# Arduino_Electronic_Load_Ver07.net
KiCad netlist of a schematic drawn in EAGLE
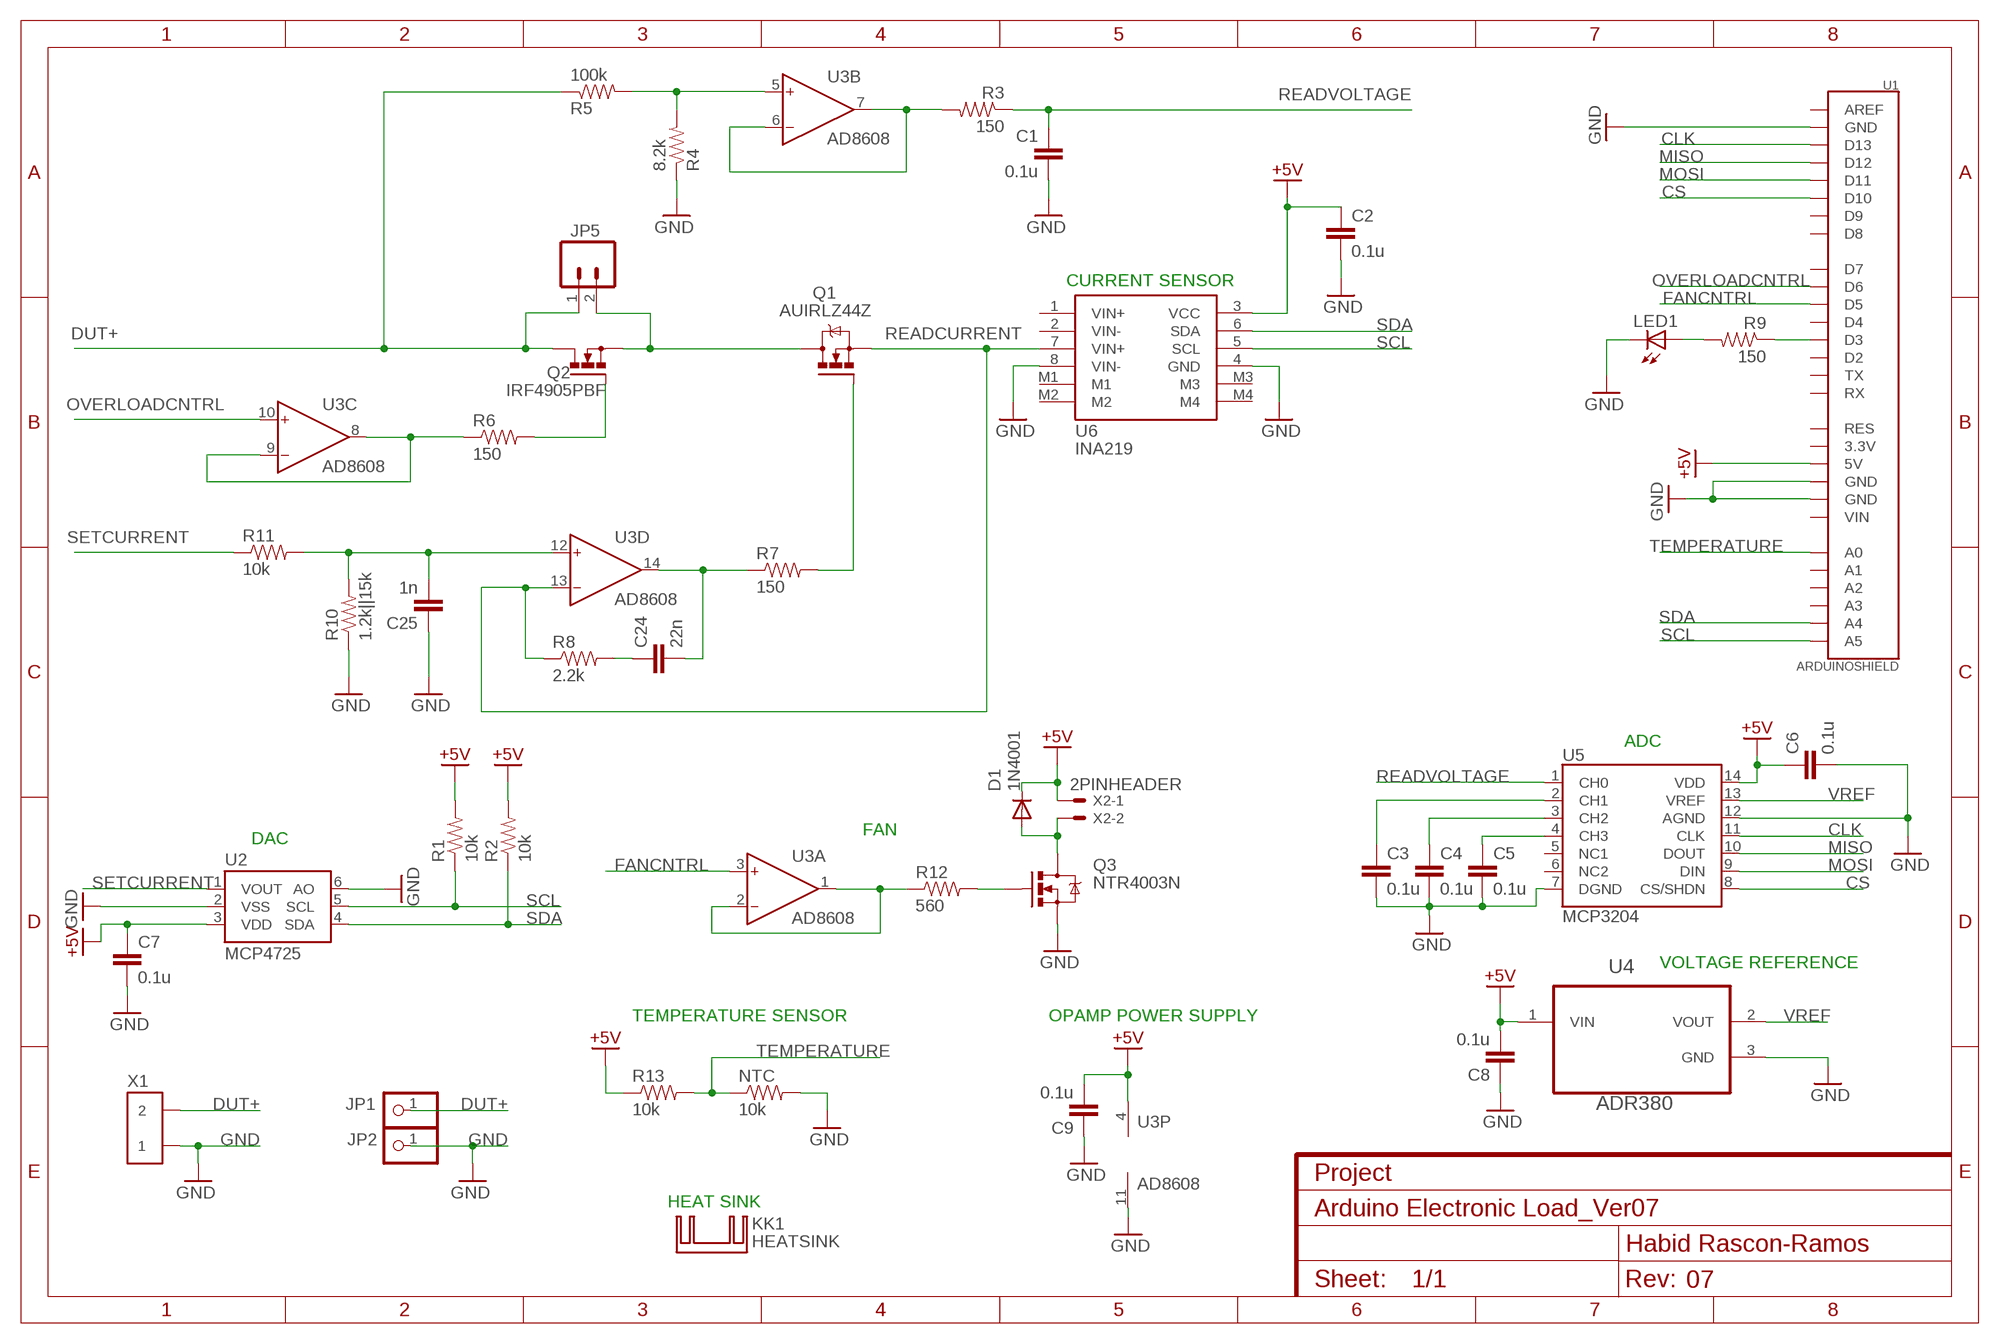
[diagram p0: schematic, sheet 1]

(export (version "E")
  (design (tool "Eeschema 10.0.6"))
  (components
    (comp (ref "C1")
      (value "0.1u")
      (footprint "eagle-import:0603-CAP")
      (description "CAP CER 0.1UF 16V X7R 0603")
      (fields
        (field (name "MANUFACTURER") "Murata Electronics North America")
        (field (name "MFG_PART_NUMBER") "GRM188R71C104KA01D")
      )
      (libsource (lib "eagle-import") (part "CAP0603-CAP"))
    )
    (comp (ref "C2")
      (value "0.1u")
      (footprint "eagle-import:0603-CAP")
      (description "CAP CER 0.1UF 16V X7R 0603")
      (fields
        (field (name "MANUFACTURER") "Murata Electronics North America")
        (field (name "MFG_PART_NUMBER") "GRM188R71C104KA01D")
      )
      (libsource (lib "eagle-import") (part "CAP0603-CAP"))
    )
    (comp (ref "C3")
      (value "0.1u")
      (footprint "eagle-import:0603-CAP")
      (description "CAP CER 0.1UF 16V X7R 0603")
      (fields
        (field (name "MANUFACTURER") "Murata Electronics North America")
        (field (name "MFG_PART_NUMBER") "GRM188R71C104KA01D")
      )
      (libsource (lib "eagle-import") (part "CAP0603-CAP"))
    )
    (comp (ref "C4")
      (value "0.1u")
      (footprint "eagle-import:0603-CAP")
      (description "CAP CER 0.1UF 16V X7R 0603")
      (fields
        (field (name "MANUFACTURER") "Murata Electronics North America")
        (field (name "MFG_PART_NUMBER") "GRM188R71C104KA01D")
      )
      (libsource (lib "eagle-import") (part "CAP0603-CAP"))
    )
    (comp (ref "C5")
      (value "0.1u")
      (footprint "eagle-import:0603-CAP")
      (description "CAP CER 0.1UF 16V X7R 0603")
      (fields
        (field (name "MANUFACTURER") "Murata Electronics North America")
        (field (name "MFG_PART_NUMBER") "GRM188R71C104KA01D")
      )
      (libsource (lib "eagle-import") (part "CAP0603-CAP"))
    )
    (comp (ref "C6")
      (value "0.1u")
      (footprint "eagle-import:0603-CAP")
      (description "CAP CER 0.1UF 16V X7R 0603")
      (fields
        (field (name "MANUFACTURER") "Murata Electronics North America")
        (field (name "MFG_PART_NUMBER") "GRM188R71C104KA01D")
      )
      (libsource (lib "eagle-import") (part "CAP0603-CAP"))
    )
    (comp (ref "C7")
      (value "0.1u")
      (footprint "eagle-import:0603-CAP")
      (description "CAP CER 0.1UF 16V X7R 0603")
      (fields
        (field (name "MANUFACTURER") "Murata Electronics North America")
        (field (name "MFG_PART_NUMBER") "GRM188R71C104KA01D")
      )
      (libsource (lib "eagle-import") (part "CAP0603-CAP"))
    )
    (comp (ref "C8")
      (value "0.1u")
      (footprint "eagle-import:0603-CAP")
      (description "CAP CER 0.1UF 16V X7R 0603")
      (fields
        (field (name "MANUFACTURER") "Murata Electronics North America")
        (field (name "MFG_PART_NUMBER") "GRM188R71C104KA01D")
      )
      (libsource (lib "eagle-import") (part "CAP0603-CAP"))
    )
    (comp (ref "C9")
      (value "0.1u")
      (footprint "eagle-import:0603-CAP")
      (description "CAP CER 0.1UF 16V X7R 0603")
      (fields
        (field (name "MANUFACTURER") "Murata Electronics North America")
        (field (name "MFG_PART_NUMBER") "GRM188R71C104KA01D")
      )
      (libsource (lib "eagle-import") (part "CAP0603-CAP"))
    )
    (comp (ref "C24")
      (value "22n")
      (footprint "eagle-import:0603-CAP")
      (description "CAP CER 0.022UF 16V X7R 0603")
      (fields
        (field (name "MANUFACTURER") "Murata Electronics North America")
        (field (name "MFG_PART_NUMBER") "GRM188R71C223KA01D")
      )
      (libsource (lib "eagle-import") (part "CAP0603-CAP"))
    )
    (comp (ref "C25")
      (value "1n")
      (footprint "eagle-import:0603-CAP")
      (description "CAP CER 1000PF 50V X7R 0603")
      (fields
        (field (name "MANUFACTURER") "Murata Electronics North America")
        (field (name "MFG_PART_NUMBER") "GRM188R71H102KA01D")
      )
      (libsource (lib "eagle-import") (part "CAP0603-CAP"))
    )
    (comp (ref "D1")
      (value "1N4001")
      (footprint "eagle-import:DIODE-1N4001")
      (description "DIODE GEN PURP 50V 1A DO41")
      (fields
        (field (name "MANUFACTURER") "Fairchild Semiconductor")
        (field (name "VENDOR_PART_NUM") "1N4001FSCT-ND")
      )
      (libsource (lib "eagle-import") (part "DIODEPTH"))
    )
    (comp (ref "JP1")
      (value "N/A")
      (footprint "eagle-import:PINHEAD_1X01")
      (libsource (lib "eagle-import") (part "PINHEAD_PINHD-1X1"))
    )
    (comp (ref "JP2")
      (value "N/A")
      (footprint "eagle-import:PINHEAD_1X01")
      (libsource (lib "eagle-import") (part "PINHEAD_PINHD-1X1"))
    )
    (comp (ref "JP5")
      (value "2PINHEADER")
      (footprint "eagle-import:1X02_LONGPADS")
      (description "CONN HEADER VERT SGL 2POS GOLD")
      (fields (field (name "MANUFACTURER") "3M") (field (name "MFG_PART_NUMBER") "961102-6404-AR"))
      (libsource (lib "eagle-import") (part "M02"))
    )
    (comp (ref "KK1")
      (value "HEATSINK")
      (footprint "eagle-import:HEATSINK_SK129-HOLE")
      (description "HEAT SINK, EXTRUDED, PCB MOUNT")
      (fields
        (field (name "MANUFACTURER") "FISCHER ELEKTRONIK")
        (field (name "MFG_PART_NUMBER") "SK 129 25,4 STS")
      )
      (libsource (lib "eagle-import") (part "HEATSINK_SK129"))
    )
    (comp (ref "LED1")
      (value "REDLED")
      (footprint "eagle-import:LED5MM")
      (description "LED RED DIFF 5MM ROUND T/H")
      (fields (field (name "MANUFACTURER") "Lite-On Inc.") (field (name "MFG_PART_NUMBER") "LTL2R3KRD-EM"))
      (libsource (lib "eagle-import") (part "LED5MM"))
    )
    (comp (ref "NTC")
      (value "10k")
      (footprint "eagle-import:0402-RES")
      (description "THERMISTOR 10K OHM NTC 0402 SMD")
      (fields
        (field (name "MANUFACTURER") "Murata Electronics North America")
        (field (name "MFG_PART_NUMBER") "NCP15XH103F03RC")
      )
      (libsource (lib "eagle-import") (part "RESISTOR0402-RES"))
    )
    (comp (ref "Q1")
      (value "AUIRLZ44Z")
      (footprint "eagle-import:TO220BV_1")
      (description "MOSFET Transistor, N Channel, 51 A, 55 V, TO-220AB")
      (fields
        (field (name "MANUFACTURER") "INTERNATIONAL RECTIFIER")
        (field (name "VENDOR_PART_NUM") "54T9019")
      )
      (libsource (lib "eagle-import") (part "IRLZ44Z"))
    )
    (comp (ref "Q2")
      (value "IRF4905PBF")
      (footprint "eagle-import:TO220BV")
      (description "MOSFET P-CH 55V 74A TO-220AB")
      (fields
        (field (name "MANUFACTURER") "Infineon Technologies Americas Corp.")
        (field (name "VENDOR_PART_NUM") "IRF4905PBF-ND")
      )
      (libsource (lib "eagle-import") (part "PMOSFET_NTO220BV"))
    )
    (comp (ref "Q3")
      (value "NTR4003N")
      (footprint "eagle-import:SOT23-3")
      (description "MOSFET N-CH 30V 500MA SOT-23")
      (fields (field (name "MANUFACTURER") "ON Semiconductor") (field (name "MFG_PART_NUMBER") "NTR4003NT1G"))
      (libsource (lib "eagle-import") (part "MOSFET-NCHANNELAO3404A"))
    )
    (comp (ref "R1")
      (value "10k")
      (footprint "eagle-import:0603-RES")
      (description "RES SMD 10K OHM 1% 1/10W 0603")
      (fields (field (name "MANUFACTURER") "Yageo") (field (name "MFG_PART_NUMBER") "RC0603FR-0710KL"))
      (libsource (lib "eagle-import") (part "RESISTOR0603-RES"))
    )
    (comp (ref "R2")
      (value "10k")
      (footprint "eagle-import:0603-RES")
      (description "RES SMD 10K OHM 1% 1/10W 0603")
      (fields (field (name "MANUFACTURER") "Yageo") (field (name "MFG_PART_NUMBER") "RC0603FR-0710KL"))
      (libsource (lib "eagle-import") (part "RESISTOR0603-RES"))
    )
    (comp (ref "R3")
      (value "150")
      (footprint "eagle-import:0603-RES")
      (description "RES SMD 150 OHM 1% 1/10W 0603")
      (fields (field (name "MANUFACTURER") "Yageo") (field (name "MFG_PART_NUMBER") "RC0603FR-07150RL"))
      (libsource (lib "eagle-import") (part "RESISTOR0603-RES"))
    )
    (comp (ref "R4")
      (value "8.2k")
      (footprint "eagle-import:0603-RES")
      (description "RES SMD 8.2K OHM 1% 1/10W 0603")
      (fields (field (name "MANUFACTURER") "Yageo") (field (name "MFG_PART_NUMBER") "RC0603FR-078K2L"))
      (libsource (lib "eagle-import") (part "RESISTOR0603-RES"))
    )
    (comp (ref "R5")
      (value "100k")
      (footprint "eagle-import:0603-RES")
      (description "RES SMD 100K OHM 1% 1/10W 0603")
      (fields (field (name "MANUFACTURER") "Yageo") (field (name "MFG_PART_NUMBER") "RC0603FR-07100KL"))
      (libsource (lib "eagle-import") (part "RESISTOR0603-RES"))
    )
    (comp (ref "R6")
      (value "150")
      (footprint "eagle-import:0603-RES")
      (description "RES SMD 150 OHM 1% 1/10W 0603")
      (fields (field (name "MANUFACTURER") "Yageo") (field (name "MFG_PART_NUMBER") "RC0603FR-07150RL"))
      (libsource (lib "eagle-import") (part "RESISTOR0603-RES"))
    )
    (comp (ref "R7")
      (value "150")
      (footprint "eagle-import:0603-RES")
      (description "RES SMD 150 OHM 1% 1/10W 0603")
      (fields (field (name "MANUFACTURER") "Yageo") (field (name "MFG_PART_NUMBER") "RC0603FR-07150RL"))
      (libsource (lib "eagle-import") (part "RESISTOR0603-RES"))
    )
    (comp (ref "R8")
      (value "2.2k")
      (footprint "eagle-import:0603-RES")
      (description "RES SMD 2.2K OHM 1% 1/10W 0603")
      (fields (field (name "MANUFACTURER") "Yageo") (field (name "MFG_PART_NUMBER") "RC0603FR-072K2L"))
      (libsource (lib "eagle-import") (part "RESISTOR0603-RES"))
    )
    (comp (ref "R9")
      (value "150")
      (footprint "eagle-import:0603-RES")
      (description "RES SMD 150 OHM 1% 1/10W 0603")
      (fields (field (name "MANUFACTURER") "Yageo") (field (name "MFG_PART_NUMBER") "RC0603FR-07150RL"))
      (libsource (lib "eagle-import") (part "RESISTOR0603-RES"))
    )
    (comp (ref "R10")
      (value "1.2k||15k")
      (footprint "eagle-import:0603-RES")
      (description "RES SMD 1.1K OHM 1% 1/10W 0603")
      (fields (field (name "MANUFACTURER") "Yageo") (field (name "MFG_PART_NUMBER") "RC0603FR-071K1L"))
      (libsource (lib "eagle-import") (part "RESISTOR0603-RES"))
    )
    (comp (ref "R11")
      (value "10k")
      (footprint "eagle-import:0603-RES")
      (description "RES SMD 10K OHM 1% 1/10W 0603")
      (fields (field (name "MANUFACTURER") "Yageo") (field (name "MFG_PART_NUMBER") "RC0603FR-0710KL"))
      (libsource (lib "eagle-import") (part "RESISTOR0603-RES"))
    )
    (comp (ref "R12")
      (value "560")
      (footprint "eagle-import:0603-RES")
      (description "RES SMD 560 OHM 1% 1/10W 0603")
      (fields (field (name "MANUFACTURER") "Yageo") (field (name "MFG_PART_NUMBER") "RC0603FR-07560RL"))
      (libsource (lib "eagle-import") (part "RESISTOR0603-RES"))
    )
    (comp (ref "R13")
      (value "10k")
      (footprint "eagle-import:0603-RES")
      (description "RES SMD 10K OHM 1% 1/10W 0603")
      (fields (field (name "MANUFACTURER") "Yageo") (field (name "MFG_PART_NUMBER") "RC0603FR-0710KL"))
      (libsource (lib "eagle-import") (part "RESISTOR0603-RES"))
    )
    (comp (ref "U1")
      (value "ARDUINOSHIELD")
      (footprint "eagle-import:DUEMILANOVE_SHIELD")
      (libsource (lib "eagle-import") (part "ARDUINO_SHIELD"))
    )
    (comp (ref "U2")
      (value "MCP4725")
      (footprint "eagle-import:SOT23-6")
      (description "IC DAC 12BIT W/I2C SOT23A-6")
      (fields
        (field (name "MANUFACTURER") "Microchip Technology")
        (field (name "MFG_PART_NUMBER") "MCP4725A0T-E/CH")
      )
      (libsource (lib "eagle-import") (part "MCP4725SOT-23"))
    )
    (comp (ref "U3")
      (value "AD8608")
      (footprint "eagle-import:SO14")
      (description "IC OPAMP GP 10MHZ RRO 14TSSOP")
      (fields
        (field (name "MANUFACTURER") "Analog Devices Inc.")
        (field (name "MFG_PART_NUMBER") "AD8608ARUZ-REEL")
        (field (name "PACKAGE") "14-TSSOP")
        (field (name "VENDOR") "Digi-Key")
        (field (name "VENDOR_PART_NUM") "AD8608ARUZ-REELTR-ND")
      )
      (libsource (lib "eagle-import") (part "AD8608R"))
    )
    (comp (ref "U4")
      (value "ADR380")
      (footprint "eagle-import:SOT95P237X112-3N")
      (description "IC VREF SERIES 2.048V SOT23-3")
      (fields
        (field (name "MANUFACTURER") "Analog Devices Inc.")
        (field (name "MFG_PART_NUMBER") "ADR380ARTZ-REEL7")
      )
      (libsource (lib "eagle-import") (part "ADR380ARTZ-REEL7"))
    )
    (comp (ref "U5")
      (value "MCP3204")
      (footprint "eagle-import:SOIC-14")
      (description "IC ADC 12BIT 2.7V 4CH SPI 14SOIC")
      (fields
        (field (name "MANUFACTURER") "Microchip Technology")
        (field (name "MFG_PART_NUMBER") "MCP3204-CI/SL")
      )
      (libsource (lib "eagle-import") (part "MCP3204CRZ"))
    )
    (comp (ref "U6")
      (value "INA219")
      (footprint "eagle-import:INA219")
      (description "BREAKOUT INA219 DC SENS 26V 3.2A")
      (fields (field (name "MANUFACTURER") "Adafruit Industries LLC") (field (name "MFG_PART_NUMBER") "904"))
      (libsource (lib "eagle-import") (part "INA219"))
    )
    (comp (ref "X1")
      (value "2PINTERMBLOCK")
      (footprint "eagle-import:ED350_2")
      (description "TERM BLOCK 5.08MM VERT 2POS PCB")
      (fields
        (field (name "MANUFACTURER") "On Shore Technology Inc.")
        (field (name "MFG_PART_NUMBER") "OSTTC022162")
      )
      (libsource (lib "eagle-import") (part "ED350/2"))
    )
    (comp (ref "X2")
      (value "2PINHEADER")
      (footprint "eagle-import:CON-MOLEX_22-23-2021")
      (description "CONN HEADER 2POS .100 VERT TIN")
      (fields
        (field (name "MANUFACTURER") "Molex, LLC")
        (field (name "MFG_PART_NUMBER") "22232021")
        (field (name "PACKAGE") "N/A")
        (field (name "VENDOR") "Digi-Key")
        (field (name "VENDOR_PART_NUM") "WM4200-ND")
      )
      (libsource (lib "eagle-import") (part "CON-MOLEX_22-23-2021"))
    )
  )
  (nets
    (net (code "1") (name "+5V") (class "Default")
      (node (ref "C2") (pin "1") (pinfunction "1_1") (pintype "passive"))
      (node (ref "C6") (pin "1") (pinfunction "1_1") (pintype "passive"))
      (node (ref "C7") (pin "1") (pinfunction "1_1") (pintype "passive"))
      (node (ref "C8") (pin "2") (pinfunction "2_2") (pintype "passive"))
      (node (ref "C9") (pin "2") (pinfunction "2_2") (pintype "passive"))
      (node (ref "D1") (pin "C") (pinfunction "C_C") (pintype "passive"))
      (node (ref "R1") (pin "2") (pinfunction "2_2") (pintype "passive"))
      (node (ref "R13") (pin "1") (pinfunction "1_1") (pintype "passive"))
      (node (ref "R2") (pin "2") (pinfunction "2_2") (pintype "passive"))
      (node (ref "U1") (pin "5V") (pinfunction "5V_5V") (pintype "bidirectional"))
      (node (ref "U2") (pin "3") (pinfunction "VDD_3") (pintype "bidirectional"))
      (node (ref "U3") (pin "4") (pinfunction "V+_4") (pintype "power_in"))
      (node (ref "U4") (pin "1") (pinfunction "VIN_1") (pintype "passive"))
      (node (ref "U5") (pin "14") (pinfunction "VDD_14") (pintype "bidirectional"))
      (node (ref "U6") (pin "3") (pinfunction "VCC_3") (pintype "bidirectional"))
      (node (ref "X2") (pin "1") (pinfunction "S_1") (pintype "passive"))
    )
    (net (code "2") (name "/CLK") (class "Default")
      (node (ref "U1") (pin "D13") (pinfunction "D13_D13") (pintype "bidirectional"))
      (node (ref "U5") (pin "11") (pinfunction "CLK_11") (pintype "bidirectional"))
    )
    (net (code "3") (name "/CS") (class "Default")
      (node (ref "U1") (pin "D10") (pinfunction "D10_D10") (pintype "bidirectional"))
      (node (ref "U5") (pin "8") (pinfunction "CS/SHDN_8") (pintype "bidirectional"))
    )
    (net (code "4") (name "/DUT+") (class "Default")
      (node (ref "JP1") (pin "1") (pinfunction "1_1") (pintype "passive"))
      (node (ref "JP5") (pin "1") (pinfunction "1_1") (pintype "passive"))
      (node (ref "Q2") (pin "D") (pinfunction "D_D") (pintype "passive"))
      (node (ref "R5") (pin "1") (pinfunction "1_1") (pintype "passive"))
      (node (ref "X1") (pin "P$2") (pinfunction "2_P$2") (pintype "bidirectional"))
    )
    (net (code "5") (name "/FANCNTRL") (class "Default")
      (node (ref "U1") (pin "D5") (pinfunction "D5_D5") (pintype "bidirectional"))
      (node (ref "U3") (pin "3") (pinfunction "IN+_3") (pintype "input"))
    )
    (net (code "6") (name "/MISO") (class "Default")
      (node (ref "U1") (pin "D12") (pinfunction "D12_D12") (pintype "bidirectional"))
      (node (ref "U5") (pin "10") (pinfunction "DOUT_10") (pintype "bidirectional"))
    )
    (net (code "7") (name "/MOSI") (class "Default")
      (node (ref "U1") (pin "D11") (pinfunction "D11_D11") (pintype "bidirectional"))
      (node (ref "U5") (pin "9") (pinfunction "DIN_9") (pintype "bidirectional"))
    )
    (net (code "8") (name "/OVERLOADCNTRL") (class "Default")
      (node (ref "U1") (pin "D6") (pinfunction "D6_D6") (pintype "bidirectional"))
      (node (ref "U3") (pin "10") (pinfunction "IN+_10") (pintype "input"))
    )
    (net (code "9") (name "/READCURRENT") (class "Default")
      (node (ref "Q1") (pin "S") (pinfunction "S_S") (pintype "passive"))
      (node (ref "R8") (pin "1") (pinfunction "1_1") (pintype "passive"))
      (node (ref "U3") (pin "13") (pinfunction "IN-_13") (pintype "input"))
      (node (ref "U6") (pin "7") (pinfunction "VIN+_7") (pintype "bidirectional"))
    )
    (net (code "10") (name "/READVOLTAGE") (class "Default")
      (node (ref "C1") (pin "1") (pinfunction "1_1") (pintype "passive"))
      (node (ref "R3") (pin "1") (pinfunction "1_1") (pintype "passive"))
      (node (ref "U5") (pin "1") (pinfunction "CH0_1") (pintype "bidirectional"))
    )
    (net (code "11") (name "/SCL") (class "Default")
      (node (ref "R1") (pin "1") (pinfunction "1_1") (pintype "passive"))
      (node (ref "U1") (pin "A5") (pinfunction "A5_A5") (pintype "bidirectional"))
      (node (ref "U2") (pin "5") (pinfunction "SCL_5") (pintype "bidirectional"))
      (node (ref "U6") (pin "5") (pinfunction "SCL_5") (pintype "bidirectional"))
    )
    (net (code "12") (name "/SDA") (class "Default")
      (node (ref "R2") (pin "1") (pinfunction "1_1") (pintype "passive"))
      (node (ref "U1") (pin "A4") (pinfunction "A4_A4") (pintype "bidirectional"))
      (node (ref "U2") (pin "4") (pinfunction "SDA_4") (pintype "bidirectional"))
      (node (ref "U6") (pin "6") (pinfunction "SDA_6") (pintype "bidirectional"))
    )
    (net (code "13") (name "/SETCURRENT") (class "Default")
      (node (ref "R11") (pin "1") (pinfunction "1_1") (pintype "passive"))
      (node (ref "U2") (pin "1") (pinfunction "VOUT_1") (pintype "bidirectional"))
    )
    (net (code "14") (name "/TEMPERATURE") (class "Default")
      (node (ref "NTC") (pin "1") (pinfunction "1_1") (pintype "passive"))
      (node (ref "R13") (pin "2") (pinfunction "2_2") (pintype "passive"))
      (node (ref "U1") (pin "A0") (pinfunction "A0_A0") (pintype "bidirectional"))
    )
    (net (code "15") (name "/VREF") (class "Default")
      (node (ref "U4") (pin "2") (pinfunction "VOUT_2") (pintype "passive"))
      (node (ref "U5") (pin "13") (pinfunction "VREF_13") (pintype "bidirectional"))
    )
    (net (code "16") (name "GND") (class "Default")
      (node (ref "C1") (pin "2") (pinfunction "2_2") (pintype "passive"))
      (node (ref "C2") (pin "2") (pinfunction "2_2") (pintype "passive"))
      (node (ref "C25") (pin "1") (pinfunction "1_1") (pintype "passive"))
      (node (ref "C3") (pin "2") (pinfunction "2_2") (pintype "passive"))
      (node (ref "C4") (pin "2") (pinfunction "2_2") (pintype "passive"))
      (node (ref "C5") (pin "2") (pinfunction "2_2") (pintype "passive"))
      (node (ref "C6") (pin "2") (pinfunction "2_2") (pintype "passive"))
      (node (ref "C7") (pin "2") (pinfunction "2_2") (pintype "passive"))
      (node (ref "C8") (pin "1") (pinfunction "1_1") (pintype "passive"))
      (node (ref "C9") (pin "1") (pinfunction "1_1") (pintype "passive"))
      (node (ref "JP2") (pin "1") (pinfunction "1_1") (pintype "passive"))
      (node (ref "LED1") (pin "K") (pinfunction "C_K") (pintype "passive"))
      (node (ref "NTC") (pin "2") (pinfunction "2_2") (pintype "passive"))
      (node (ref "Q3") (pin "2") (pinfunction "S_2") (pintype "passive"))
      (node (ref "R10") (pin "1") (pinfunction "1_1") (pintype "passive"))
      (node (ref "R4") (pin "1") (pinfunction "1_1") (pintype "passive"))
      (node (ref "U1") (pin "GND@0") (pinfunction "GND_GND@0") (pintype "bidirectional"))
      (node (ref "U1") (pin "GND@1") (pinfunction "GND_GND@1") (pintype "bidirectional"))
      (node (ref "U1") (pin "GND@2") (pinfunction "GND_GND@2") (pintype "bidirectional"))
      (node (ref "U2") (pin "2") (pinfunction "VSS_2") (pintype "bidirectional"))
      (node (ref "U2") (pin "6") (pinfunction "AO_6") (pintype "bidirectional"))
      (node (ref "U3") (pin "11") (pinfunction "V-_11") (pintype "power_in"))
      (node (ref "U4") (pin "3") (pinfunction "GND_3") (pintype "passive"))
      (node (ref "U5") (pin "12") (pinfunction "AGND_12") (pintype "bidirectional"))
      (node (ref "U5") (pin "7") (pinfunction "DGND_7") (pintype "bidirectional"))
      (node (ref "U6") (pin "4") (pinfunction "GND_4") (pintype "bidirectional"))
      (node (ref "U6") (pin "8") (pinfunction "VIN-_8") (pintype "bidirectional"))
      (node (ref "X1") (pin "P$1") (pinfunction "1_P$1") (pintype "bidirectional"))
    )
    (net (code "17") (name "Net-(C24-Pad1)") (class "Default")
      (node (ref "C24") (pin "1") (pinfunction "1_1") (pintype "passive"))
      (node (ref "R8") (pin "2") (pinfunction "2_2") (pintype "passive"))
    )
    (net (code "18") (name "Net-(JP5-Pad2)") (class "Default")
      (node (ref "JP5") (pin "2") (pinfunction "2_2") (pintype "passive"))
      (node (ref "Q1") (pin "D") (pinfunction "D_D") (pintype "passive"))
      (node (ref "Q2") (pin "S") (pinfunction "S_S") (pintype "passive"))
    )
    (net (code "19") (name "Net-(LED1-PadA)") (class "Default")
      (node (ref "LED1") (pin "A") (pinfunction "A_A") (pintype "passive"))
      (node (ref "R9") (pin "2") (pinfunction "2_2") (pintype "passive"))
    )
    (net (code "20") (name "Net-(Q1-PadG)") (class "Default")
      (node (ref "Q1") (pin "G") (pinfunction "G_G") (pintype "passive"))
      (node (ref "R7") (pin "2") (pinfunction "2_2") (pintype "passive"))
    )
    (net (code "21") (name "Net-(Q2-PadG)") (class "Default")
      (node (ref "Q2") (pin "G") (pinfunction "G_G") (pintype "passive"))
      (node (ref "R6") (pin "2") (pinfunction "2_2") (pintype "passive"))
    )
    (net (code "22") (name "Net-(Q3-D)") (class "Default")
      (node (ref "D1") (pin "A") (pinfunction "A_A") (pintype "passive"))
      (node (ref "Q3") (pin "3") (pinfunction "D_3") (pintype "passive"))
      (node (ref "X2") (pin "2") (pinfunction "S_2") (pintype "passive"))
    )
    (net (code "23") (name "Net-(Q3-G)") (class "Default")
      (node (ref "Q3") (pin "1") (pinfunction "G_1") (pintype "passive"))
      (node (ref "R12") (pin "2") (pinfunction "2_2") (pintype "passive"))
    )
    (net (code "24") (name "Net-(R9-Pad1)") (class "Default")
      (node (ref "R9") (pin "1") (pinfunction "1_1") (pintype "passive"))
      (node (ref "U1") (pin "D3") (pinfunction "D3_D3") (pintype "bidirectional"))
    )
    (net (code "25") (name "Net-(U3A-IN-)") (class "Default")
      (node (ref "R12") (pin "1") (pinfunction "1_1") (pintype "passive"))
      (node (ref "U3") (pin "1") (pinfunction "OUT_1") (pintype "output"))
      (node (ref "U3") (pin "2") (pinfunction "IN-_2") (pintype "input"))
    )
    (net (code "26") (name "Net-(U3B-IN+)") (class "Default")
      (node (ref "R4") (pin "2") (pinfunction "2_2") (pintype "passive"))
      (node (ref "R5") (pin "2") (pinfunction "2_2") (pintype "passive"))
      (node (ref "U3") (pin "5") (pinfunction "IN+_5") (pintype "input"))
    )
    (net (code "27") (name "Net-(U3B-IN-)") (class "Default")
      (node (ref "R3") (pin "2") (pinfunction "2_2") (pintype "passive"))
      (node (ref "U3") (pin "6") (pinfunction "IN-_6") (pintype "input"))
      (node (ref "U3") (pin "7") (pinfunction "OUT_7") (pintype "output"))
    )
    (net (code "28") (name "Net-(U3C-IN-)") (class "Default")
      (node (ref "R6") (pin "1") (pinfunction "1_1") (pintype "passive"))
      (node (ref "U3") (pin "8") (pinfunction "OUT_8") (pintype "output"))
      (node (ref "U3") (pin "9") (pinfunction "IN-_9") (pintype "input"))
    )
    (net (code "29") (name "Net-(U3D-IN+)") (class "Default")
      (node (ref "C25") (pin "2") (pinfunction "2_2") (pintype "passive"))
      (node (ref "R10") (pin "2") (pinfunction "2_2") (pintype "passive"))
      (node (ref "R11") (pin "2") (pinfunction "2_2") (pintype "passive"))
      (node (ref "U3") (pin "12") (pinfunction "IN+_12") (pintype "input"))
    )
    (net (code "30") (name "Net-(U3D-OUT)") (class "Default")
      (node (ref "C24") (pin "2") (pinfunction "2_2") (pintype "passive"))
      (node (ref "R7") (pin "1") (pinfunction "1_1") (pintype "passive"))
      (node (ref "U3") (pin "14") (pinfunction "OUT_14") (pintype "output"))
    )
    (net (code "31") (name "Net-(U5-CH1)") (class "Default")
      (node (ref "C3") (pin "1") (pinfunction "1_1") (pintype "passive"))
      (node (ref "U5") (pin "2") (pinfunction "CH1_2") (pintype "bidirectional"))
    )
    (net (code "32") (name "Net-(U5-CH2)") (class "Default")
      (node (ref "C4") (pin "1") (pinfunction "1_1") (pintype "passive"))
      (node (ref "U5") (pin "3") (pinfunction "CH2_3") (pintype "bidirectional"))
    )
    (net (code "33") (name "Net-(U5-CH3)") (class "Default")
      (node (ref "C5") (pin "1") (pinfunction "1_1") (pintype "passive"))
      (node (ref "U5") (pin "4") (pinfunction "CH3_4") (pintype "bidirectional"))
    )
    (net (code "34") (name "unconnected-(U1-Pad3.3V)") (class "Default")
      (node (ref "U1") (pin "3.3V") (pinfunction "3.3V_3.3V") (pintype "bidirectional"))
    )
    (net (code "35") (name "unconnected-(U1-PadA1)") (class "Default")
      (node (ref "U1") (pin "A1") (pinfunction "A1_A1") (pintype "bidirectional"))
    )
    (net (code "36") (name "unconnected-(U1-PadA2)") (class "Default")
      (node (ref "U1") (pin "A2") (pinfunction "A2_A2") (pintype "bidirectional"))
    )
    (net (code "37") (name "unconnected-(U1-PadA3)") (class "Default")
      (node (ref "U1") (pin "A3") (pinfunction "A3_A3") (pintype "bidirectional"))
    )
    (net (code "38") (name "unconnected-(U1-PadAREF)") (class "Default")
      (node (ref "U1") (pin "AREF") (pinfunction "AREF_AREF") (pintype "bidirectional"))
    )
    (net (code "39") (name "unconnected-(U1-PadD2)") (class "Default")
      (node (ref "U1") (pin "D2") (pinfunction "D2_D2") (pintype "bidirectional"))
    )
    (net (code "40") (name "unconnected-(U1-PadD4)") (class "Default")
      (node (ref "U1") (pin "D4") (pinfunction "D4_D4") (pintype "bidirectional"))
    )
    (net (code "41") (name "unconnected-(U1-PadD7)") (class "Default")
      (node (ref "U1") (pin "D7") (pinfunction "D7_D7") (pintype "bidirectional"))
    )
    (net (code "42") (name "unconnected-(U1-PadD8)") (class "Default")
      (node (ref "U1") (pin "D8") (pinfunction "D8_D8") (pintype "bidirectional"))
    )
    (net (code "43") (name "unconnected-(U1-PadD9)") (class "Default")
      (node (ref "U1") (pin "D9") (pinfunction "D9_D9") (pintype "bidirectional"))
    )
    (net (code "44") (name "unconnected-(U1-PadRES)") (class "Default")
      (node (ref "U1") (pin "RES") (pinfunction "RES_RES") (pintype "bidirectional"))
    )
    (net (code "45") (name "unconnected-(U1-PadRX)") (class "Default")
      (node (ref "U1") (pin "RX") (pinfunction "RX_RX") (pintype "bidirectional"))
    )
    (net (code "46") (name "unconnected-(U1-PadTX)") (class "Default")
      (node (ref "U1") (pin "TX") (pinfunction "TX_TX") (pintype "bidirectional"))
    )
    (net (code "47") (name "unconnected-(U1-PadVIN)") (class "Default")
      (node (ref "U1") (pin "VIN") (pinfunction "VIN_VIN") (pintype "bidirectional"))
    )
    (net (code "48") (name "unconnected-(U5-NC1-Pad5)") (class "Default")
      (node (ref "U5") (pin "5") (pinfunction "NC1_5") (pintype "bidirectional"))
    )
    (net (code "49") (name "unconnected-(U5-NC2-Pad6)") (class "Default")
      (node (ref "U5") (pin "6") (pinfunction "NC2_6") (pintype "bidirectional"))
    )
    (net (code "50") (name "unconnected-(U6-PadM1)") (class "Default")
      (node (ref "U6") (pin "M1") (pinfunction "M1_M1") (pintype "bidirectional"))
    )
    (net (code "51") (name "unconnected-(U6-PadM2)") (class "Default")
      (node (ref "U6") (pin "M2") (pinfunction "M2_M2") (pintype "bidirectional"))
    )
    (net (code "52") (name "unconnected-(U6-PadM3)") (class "Default")
      (node (ref "U6") (pin "M3") (pinfunction "M3_M3") (pintype "bidirectional"))
    )
    (net (code "53") (name "unconnected-(U6-PadM4)") (class "Default")
      (node (ref "U6") (pin "M4") (pinfunction "M4_M4") (pintype "bidirectional"))
    )
    (net (code "54") (name "unconnected-(U6-VIN+-Pad1)") (class "Default")
      (node (ref "U6") (pin "1") (pinfunction "VIN+_1") (pintype "bidirectional"))
    )
    (net (code "55") (name "unconnected-(U6-VIN--Pad2)") (class "Default")
      (node (ref "U6") (pin "2") (pinfunction "VIN-_2") (pintype "bidirectional"))
    )
  )
)
